# fixture-sewer-osh.net
KiCad netlist of a schematic drawn in EAGLE
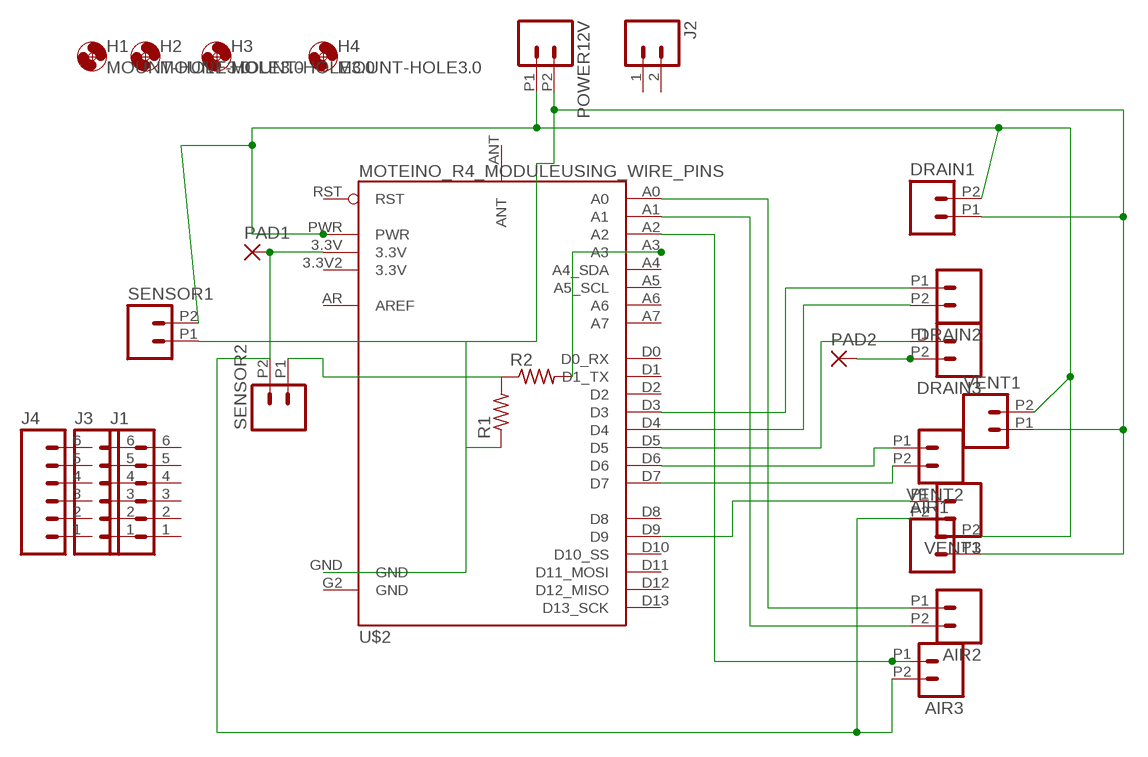
[diagram p0: schematic, sheet 1]

(export (version "E")
  (design (tool "Eeschema 10.0.6"))
  (components
    (comp (ref "AIR1")
      (value "M022.54MM_SCREWTERM")
      (footprint "eagle-import:1X02_2.54_SCREWTERM")
      (libsource (lib "eagle-import") (part "M022.54MM_SCREWTERM"))
    )
    (comp (ref "AIR2")
      (value "M022.54MM_SCREWTERM")
      (footprint "eagle-import:1X02_2.54_SCREWTERM")
      (libsource (lib "eagle-import") (part "M022.54MM_SCREWTERM"))
    )
    (comp (ref "AIR3")
      (value "M022.54MM_SCREWTERM")
      (footprint "eagle-import:1X02_2.54_SCREWTERM")
      (libsource (lib "eagle-import") (part "M022.54MM_SCREWTERM"))
    )
    (comp (ref "DRAIN1")
      (value "M022.54MM_SCREWTERM")
      (footprint "eagle-import:1X02_2.54_SCREWTERM")
      (libsource (lib "eagle-import") (part "M022.54MM_SCREWTERM"))
    )
    (comp (ref "DRAIN2")
      (value "M022.54MM_SCREWTERM")
      (footprint "eagle-import:1X02_2.54_SCREWTERM")
      (libsource (lib "eagle-import") (part "M022.54MM_SCREWTERM"))
    )
    (comp (ref "DRAIN3")
      (value "M022.54MM_SCREWTERM")
      (footprint "eagle-import:1X02_2.54_SCREWTERM")
      (libsource (lib "eagle-import") (part "M022.54MM_SCREWTERM"))
    )
    (comp (ref "H1")
      (value "MOUNT-HOLE3.0")
      (footprint "eagle-import:3,0")
      (libsource (lib "eagle-import") (part "MOUNT-HOLE3.0"))
    )
    (comp (ref "H2")
      (value "MOUNT-HOLE3.0")
      (footprint "eagle-import:3,0")
      (libsource (lib "eagle-import") (part "MOUNT-HOLE3.0"))
    )
    (comp (ref "H3")
      (value "MOUNT-HOLE3.0")
      (footprint "eagle-import:3,0")
      (libsource (lib "eagle-import") (part "MOUNT-HOLE3.0"))
    )
    (comp (ref "H4")
      (value "MOUNT-HOLE3.0")
      (footprint "eagle-import:3,0")
      (libsource (lib "eagle-import") (part "MOUNT-HOLE3.0"))
    )
    (comp (ref "J1")
      (value "M06LOCK_LONGPADS")
      (footprint "eagle-import:1X06_LOCK_LONGPADS")
      (libsource (lib "eagle-import") (part "M06LOCK_LONGPADS"))
    )
    (comp (ref "J2")
      (value "M025MM")
      (footprint "eagle-import:SCREWTERMINAL-5MM-2")
      (libsource (lib "eagle-import") (part "M025MM"))
    )
    (comp (ref "J3")
      (value "M06LOCK_LONGPADS")
      (footprint "eagle-import:1X06_LOCK_LONGPADS")
      (libsource (lib "eagle-import") (part "M06LOCK_LONGPADS"))
    )
    (comp (ref "J4")
      (value "M06LOCK_LONGPADS")
      (footprint "eagle-import:1X06_LOCK_LONGPADS")
      (libsource (lib "eagle-import") (part "M06LOCK_LONGPADS"))
    )
    (comp (ref "PAD1")
      (value "2,15/1,0")
      (footprint "eagle-import:2,15_1,0")
      (libsource (lib "eagle-import") (part "2,15/1,0"))
    )
    (comp (ref "PAD2")
      (value "2,15/1,0")
      (footprint "eagle-import:2,15_1,0")
      (libsource (lib "eagle-import") (part "2,15/1,0"))
    )
    (comp (ref "POWER12V")
      (value "M022.54MM_SCREWTERM")
      (footprint "eagle-import:1X02_2.54_SCREWTERM")
      (libsource (lib "eagle-import") (part "M022.54MM_SCREWTERM"))
    )
    (comp (ref "R1")
      (value "R-US_0207/10")
      (footprint "eagle-import:0207_10")
      (libsource (lib "eagle-import") (part "R-US_0207/10"))
    )
    (comp (ref "R2")
      (value "R-US_0207/10")
      (footprint "eagle-import:0207_10")
      (libsource (lib "eagle-import") (part "R-US_0207/10"))
    )
    (comp (ref "SENSOR1")
      (value "M022.54MM_SCREWTERM")
      (footprint "eagle-import:1X02_2.54_SCREWTERM")
      (libsource (lib "eagle-import") (part "M022.54MM_SCREWTERM"))
    )
    (comp (ref "SENSOR2")
      (value "M022.54MM_SCREWTERM")
      (footprint "eagle-import:1X02_2.54_SCREWTERM")
      (libsource (lib "eagle-import") (part "M022.54MM_SCREWTERM"))
    )
    (comp (ref "U$2")
      (value "MOTEINO_R4_MODULEUSING_WIRE_PINS")
      (footprint "eagle-import:MOTEINO_R4_WIRE")
      (libsource (lib "eagle-import") (part "MOTEINO_R4_MODULEUSING_WIRE_PINS"))
    )
    (comp (ref "VENT1")
      (value "M022.54MM_SCREWTERM")
      (footprint "eagle-import:1X02_2.54_SCREWTERM")
      (libsource (lib "eagle-import") (part "M022.54MM_SCREWTERM"))
    )
    (comp (ref "VENT2")
      (value "M022.54MM_SCREWTERM")
      (footprint "eagle-import:1X02_2.54_SCREWTERM")
      (libsource (lib "eagle-import") (part "M022.54MM_SCREWTERM"))
    )
    (comp (ref "VENT3")
      (value "M022.54MM_SCREWTERM")
      (footprint "eagle-import:1X02_2.54_SCREWTERM")
      (libsource (lib "eagle-import") (part "M022.54MM_SCREWTERM"))
    )
  )
  (nets
    (net (code "1") (name "/GND") (class "Default")
      (node (ref "U$2") (pin "G2") (pinfunction "GND_G2") (pintype "power_in"))
    )
    (net (code "2") (name "Net-(AIR1-1)") (class "Default")
      (node (ref "AIR1") (pin "P1") (pinfunction "1_P1") (pintype "passive"))
      (node (ref "DRAIN1") (pin "P1") (pinfunction "1_P1") (pintype "passive"))
      (node (ref "POWER12V") (pin "P2") (pinfunction "2_P2") (pintype "passive"))
      (node (ref "R1") (pin "1") (pinfunction "1_1") (pintype "passive"))
      (node (ref "SENSOR1") (pin "P1") (pinfunction "1_P1") (pintype "passive"))
      (node (ref "U$2") (pin "GND") (pinfunction "GND_GND") (pintype "power_in"))
      (node (ref "VENT1") (pin "P1") (pinfunction "1_P1") (pintype "passive"))
    )
    (net (code "3") (name "Net-(AIR1-2)") (class "Default")
      (node (ref "AIR1") (pin "P2") (pinfunction "2_P2") (pintype "passive"))
      (node (ref "DRAIN1") (pin "P2") (pinfunction "2_P2") (pintype "passive"))
      (node (ref "POWER12V") (pin "P1") (pinfunction "1_P1") (pintype "passive"))
      (node (ref "SENSOR1") (pin "P2") (pinfunction "2_P2") (pintype "passive"))
      (node (ref "U$2") (pin "PWR") (pinfunction "PWR_PWR") (pintype "passive"))
      (node (ref "VENT1") (pin "P2") (pinfunction "2_P2") (pintype "passive"))
    )
    (net (code "4") (name "Net-(AIR2-1)") (class "Default")
      (node (ref "AIR2") (pin "P1") (pinfunction "1_P1") (pintype "passive"))
      (node (ref "U$2") (pin "A0") (pinfunction "A0_A0") (pintype "bidirectional"))
    )
    (net (code "5") (name "Net-(AIR2-2)") (class "Default")
      (node (ref "AIR2") (pin "P2") (pinfunction "2_P2") (pintype "passive"))
      (node (ref "U$2") (pin "A1") (pinfunction "A1_A1") (pintype "bidirectional"))
    )
    (net (code "6") (name "Net-(AIR3-1)") (class "Default")
      (node (ref "AIR3") (pin "P1") (pinfunction "1_P1") (pintype "passive"))
      (node (ref "U$2") (pin "A2") (pinfunction "A2_A2") (pintype "bidirectional"))
    )
    (net (code "7") (name "Net-(AIR3-2)") (class "Default")
      (node (ref "AIR3") (pin "P2") (pinfunction "2_P2") (pintype "passive"))
      (node (ref "PAD1") (pin "1") (pinfunction "P_1") (pintype "passive"))
      (node (ref "SENSOR2") (pin "P2") (pinfunction "2_P2") (pintype "passive"))
      (node (ref "U$2") (pin "3.3V") (pinfunction "3.3V_3.3V") (pintype "passive"))
      (node (ref "VENT3") (pin "P2") (pinfunction "2_P2") (pintype "passive"))
    )
    (net (code "8") (name "Net-(DRAIN2-1)") (class "Default")
      (node (ref "DRAIN2") (pin "P1") (pinfunction "1_P1") (pintype "passive"))
      (node (ref "U$2") (pin "D3") (pinfunction "D3_D3") (pintype "bidirectional"))
    )
    (net (code "9") (name "Net-(DRAIN2-2)") (class "Default")
      (node (ref "DRAIN2") (pin "P2") (pinfunction "2_P2") (pintype "passive"))
      (node (ref "U$2") (pin "D4") (pinfunction "D4_D4") (pintype "bidirectional"))
    )
    (net (code "10") (name "Net-(DRAIN3-1)") (class "Default")
      (node (ref "DRAIN3") (pin "P1") (pinfunction "1_P1") (pintype "passive"))
      (node (ref "U$2") (pin "D5") (pinfunction "D5_D5") (pintype "bidirectional"))
    )
    (net (code "11") (name "Net-(DRAIN3-2)") (class "Default")
      (node (ref "DRAIN3") (pin "P2") (pinfunction "2_P2") (pintype "passive"))
      (node (ref "PAD2") (pin "1") (pinfunction "P_1") (pintype "passive"))
    )
    (net (code "12") (name "Net-(R2-Pad2)") (class "Default")
      (node (ref "R2") (pin "2") (pinfunction "2_2") (pintype "passive"))
      (node (ref "U$2") (pin "A3") (pinfunction "A3_A3") (pintype "bidirectional"))
    )
    (net (code "13") (name "Net-(SENSOR2-1)") (class "Default")
      (node (ref "R1") (pin "2") (pinfunction "2_2") (pintype "passive"))
      (node (ref "R2") (pin "1") (pinfunction "1_1") (pintype "passive"))
      (node (ref "SENSOR2") (pin "P1") (pinfunction "1_P1") (pintype "passive"))
    )
    (net (code "14") (name "Net-(VENT2-1)") (class "Default")
      (node (ref "U$2") (pin "D6") (pinfunction "D6_D6") (pintype "bidirectional"))
      (node (ref "VENT2") (pin "P1") (pinfunction "1_P1") (pintype "passive"))
    )
    (net (code "15") (name "Net-(VENT2-2)") (class "Default")
      (node (ref "U$2") (pin "D7") (pinfunction "D7_D7") (pintype "bidirectional"))
      (node (ref "VENT2") (pin "P2") (pinfunction "2_P2") (pintype "passive"))
    )
    (net (code "16") (name "Net-(VENT3-1)") (class "Default")
      (node (ref "U$2") (pin "D9") (pinfunction "D9_D9") (pintype "bidirectional"))
      (node (ref "VENT3") (pin "P1") (pinfunction "1_P1") (pintype "passive"))
    )
    (net (code "17") (name "unconnected-(J1-Pad1)") (class "Default")
      (node (ref "J1") (pin "1") (pinfunction "1_1") (pintype "passive"))
    )
    (net (code "18") (name "unconnected-(J1-Pad2)") (class "Default")
      (node (ref "J1") (pin "2") (pinfunction "2_2") (pintype "passive"))
    )
    (net (code "19") (name "unconnected-(J1-Pad3)") (class "Default")
      (node (ref "J1") (pin "3") (pinfunction "3_3") (pintype "passive"))
    )
    (net (code "20") (name "unconnected-(J1-Pad4)") (class "Default")
      (node (ref "J1") (pin "4") (pinfunction "4_4") (pintype "passive"))
    )
    (net (code "21") (name "unconnected-(J1-Pad5)") (class "Default")
      (node (ref "J1") (pin "5") (pinfunction "5_5") (pintype "passive"))
    )
    (net (code "22") (name "unconnected-(J1-Pad6)") (class "Default")
      (node (ref "J1") (pin "6") (pinfunction "6_6") (pintype "passive"))
    )
    (net (code "23") (name "unconnected-(J2-Pad1)") (class "Default")
      (node (ref "J2") (pin "1") (pinfunction "1_1") (pintype "passive"))
    )
    (net (code "24") (name "unconnected-(J2-Pad2)") (class "Default")
      (node (ref "J2") (pin "2") (pinfunction "2_2") (pintype "passive"))
    )
    (net (code "25") (name "unconnected-(J3-Pad1)") (class "Default")
      (node (ref "J3") (pin "1") (pinfunction "1_1") (pintype "passive"))
    )
    (net (code "26") (name "unconnected-(J3-Pad2)") (class "Default")
      (node (ref "J3") (pin "2") (pinfunction "2_2") (pintype "passive"))
    )
    (net (code "27") (name "unconnected-(J3-Pad3)") (class "Default")
      (node (ref "J3") (pin "3") (pinfunction "3_3") (pintype "passive"))
    )
    (net (code "28") (name "unconnected-(J3-Pad4)") (class "Default")
      (node (ref "J3") (pin "4") (pinfunction "4_4") (pintype "passive"))
    )
    (net (code "29") (name "unconnected-(J3-Pad5)") (class "Default")
      (node (ref "J3") (pin "5") (pinfunction "5_5") (pintype "passive"))
    )
    (net (code "30") (name "unconnected-(J3-Pad6)") (class "Default")
      (node (ref "J3") (pin "6") (pinfunction "6_6") (pintype "passive"))
    )
    (net (code "31") (name "unconnected-(J4-Pad1)") (class "Default")
      (node (ref "J4") (pin "1") (pinfunction "1_1") (pintype "passive"))
    )
    (net (code "32") (name "unconnected-(J4-Pad2)") (class "Default")
      (node (ref "J4") (pin "2") (pinfunction "2_2") (pintype "passive"))
    )
    (net (code "33") (name "unconnected-(J4-Pad3)") (class "Default")
      (node (ref "J4") (pin "3") (pinfunction "3_3") (pintype "passive"))
    )
    (net (code "34") (name "unconnected-(J4-Pad4)") (class "Default")
      (node (ref "J4") (pin "4") (pinfunction "4_4") (pintype "passive"))
    )
    (net (code "35") (name "unconnected-(J4-Pad5)") (class "Default")
      (node (ref "J4") (pin "5") (pinfunction "5_5") (pintype "passive"))
    )
    (net (code "36") (name "unconnected-(J4-Pad6)") (class "Default")
      (node (ref "J4") (pin "6") (pinfunction "6_6") (pintype "passive"))
    )
    (net (code "37") (name "unconnected-(U$2-3.3V-Pad3.3V2)") (class "Default")
      (node (ref "U$2") (pin "3.3V2") (pinfunction "3.3V_3.3V2") (pintype "passive"))
    )
    (net (code "38") (name "unconnected-(U$2-A4_SDA-PadA4)") (class "Default")
      (node (ref "U$2") (pin "A4") (pinfunction "A4_SDA_A4") (pintype "bidirectional"))
    )
    (net (code "39") (name "unconnected-(U$2-A5_SCL-PadA5)") (class "Default")
      (node (ref "U$2") (pin "A5") (pinfunction "A5_SCL_A5") (pintype "bidirectional"))
    )
    (net (code "40") (name "unconnected-(U$2-AREF-PadAR)") (class "Default")
      (node (ref "U$2") (pin "AR") (pinfunction "AREF_AR") (pintype "bidirectional"))
    )
    (net (code "41") (name "unconnected-(U$2-D0_RX-PadD0)") (class "Default")
      (node (ref "U$2") (pin "D0") (pinfunction "D0_RX_D0") (pintype "bidirectional"))
    )
    (net (code "42") (name "unconnected-(U$2-D1_TX-PadD1)") (class "Default")
      (node (ref "U$2") (pin "D1") (pinfunction "D1_TX_D1") (pintype "bidirectional"))
    )
    (net (code "43") (name "unconnected-(U$2-D10_SS-PadD10)") (class "Default")
      (node (ref "U$2") (pin "D10") (pinfunction "D10_SS_D10") (pintype "bidirectional"))
    )
    (net (code "44") (name "unconnected-(U$2-D11_MOSI-PadD11)") (class "Default")
      (node (ref "U$2") (pin "D11") (pinfunction "D11_MOSI_D11") (pintype "bidirectional"))
    )
    (net (code "45") (name "unconnected-(U$2-D12_MISO-PadD12)") (class "Default")
      (node (ref "U$2") (pin "D12") (pinfunction "D12_MISO_D12") (pintype "bidirectional"))
    )
    (net (code "46") (name "unconnected-(U$2-D13_SCK-PadD13)") (class "Default")
      (node (ref "U$2") (pin "D13") (pinfunction "D13_SCK_D13") (pintype "bidirectional"))
    )
    (net (code "47") (name "unconnected-(U$2-PadA6)") (class "Default")
      (node (ref "U$2") (pin "A6") (pinfunction "A6_A6") (pintype "bidirectional"))
    )
    (net (code "48") (name "unconnected-(U$2-PadA7)") (class "Default")
      (node (ref "U$2") (pin "A7") (pinfunction "A7_A7") (pintype "bidirectional"))
    )
    (net (code "49") (name "unconnected-(U$2-PadANT)") (class "Default")
      (node (ref "U$2") (pin "ANT") (pinfunction "ANT_ANT") (pintype "passive"))
    )
    (net (code "50") (name "unconnected-(U$2-PadD2)") (class "Default")
      (node (ref "U$2") (pin "D2") (pinfunction "D2_D2") (pintype "bidirectional"))
    )
    (net (code "51") (name "unconnected-(U$2-PadD8)") (class "Default")
      (node (ref "U$2") (pin "D8") (pinfunction "D8_D8") (pintype "bidirectional"))
    )
    (net (code "52") (name "unconnected-(U$2-PadRST)") (class "Default")
      (node (ref "U$2") (pin "RST") (pinfunction "RST_RST") (pintype "bidirectional"))
    )
  )
)
